# agzu.net
KiCad netlist of a schematic drawn in Altium Designer
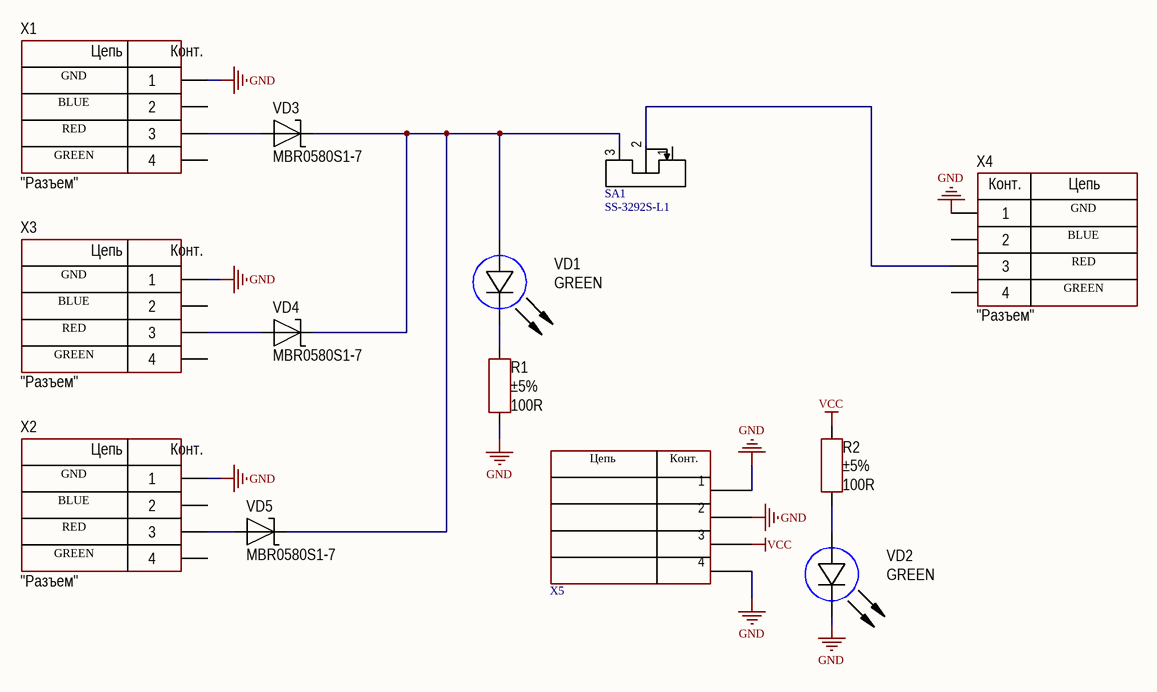
[diagram p0: agzu.SchDoc]

(export (version "E")
  (design (tool "Eeschema 10.0.6"))
  (components
    (comp (ref "R1")
      (value "100R")
      (footprint "RES: 0603")
      (fields
        (field (name "MANUFACTURER") "Yageo")
        (field (name "PARTNUMBER") "RC0603JR-07100RL")
        (field (name "VALUEMANUFACTURERPARTNUMBER") "Resistor film, 100R, ±5%, 0603, 0.1W, -55...+125°C")
        (field (name "TOLERANCE") "±5%")
      )
      (libsource (lib "Resistor") (part "Resistor_0603"))
    )
    (comp (ref "R2")
      (value "100R")
      (footprint "RES: 0603")
      (fields
        (field (name "MANUFACTURER") "Yageo")
        (field (name "PARTNUMBER") "RC0603JR-07100RL")
        (field (name "VALUEMANUFACTURERPARTNUMBER") "Resistor film, 100R, ±5%, 0603, 0.1W, -55...+125°C")
        (field (name "TOLERANCE") "±5%")
      )
      (libsource (lib "Resistor") (part "Resistor_0603"))
    )
    (comp (ref "SA1")
      (value "SS-3292S-L1")
      (footprint "SS-3292S-L1")
      (libsource (lib "switch") (part "SS-3292S-L1"))
    )
    (comp (ref "VD1")
      (value "~")
      (footprint "LED: 0805G")
      (fields
        (field (name "VALUEMANUFACTURERPARTNUMBER") "LED, *, *, *, -55...+150°C")
        (field (name "COLOR") "GREEN")
      )
      (libsource (lib "Diode") (part "LED_single"))
    )
    (comp (ref "VD2")
      (value "~")
      (footprint "LED: 1206R")
      (fields
        (field (name "VALUEMANUFACTURERPARTNUMBER") "LED, *, *, *, -55...+150°C")
        (field (name "COLOR") "GREEN")
      )
      (libsource (lib "Diode") (part "LED_single"))
    )
    (comp (ref "VD3")
      (value "~")
      (footprint "DIODE: SOD523")
      (fields
        (field (name "MANUFACTURER") "Diodes Incorporated")
        (field (name "VALUEMANUFACTURERPARTNUMBER") "Schottky diode, 80V, 500mA, 1V, 15pF, SOD-123, -55...+150°C")
        (field (name "VOLTAGE") "80V")
        (field (name "PARTNUMBER") "MBR0580S1-7")
      )
      (libsource (lib "Diode") (part "Schottky_single"))
    )
    (comp (ref "VD4")
      (value "~")
      (footprint "DIODE: SOD523")
      (fields
        (field (name "MANUFACTURER") "Diodes Incorporated")
        (field (name "VALUEMANUFACTURERPARTNUMBER") "Schottky diode, 80V, 500mA, 1V, 15pF, SOD-123, -55...+150°C")
        (field (name "VOLTAGE") "80V")
        (field (name "PARTNUMBER") "MBR0580S1-7")
      )
      (libsource (lib "Diode") (part "Schottky_single"))
    )
    (comp (ref "VD5")
      (value "~")
      (footprint "DIODE: SOD523")
      (fields
        (field (name "MANUFACTURER") "Diodes Incorporated")
        (field (name "VALUEMANUFACTURERPARTNUMBER") "Schottky diode, 80V, 500mA, 1V, 15pF, SOD-123, -55...+150°C")
        (field (name "VOLTAGE") "80V")
        (field (name "PARTNUMBER") "MBR0580S1-7")
      )
      (libsource (lib "Diode") (part "Schottky_single"))
    )
    (comp (ref "X1")
      (value "~")
      (footprint "CON: PBS-4 R")
      (fields
        (field (name "MANUFACTURER") "Connfly")
        (field (name "VALUEMANUFACTURERPARTNUMBER") "Connector, 4pin, 2.54mm, 500VAC, 3A")
        (field (name "PARTNUMBER") "PBS-4")
        (field (name "COMMENTTEXT") "\"Разъем\"")
      )
      (libsource (lib "Connector") (part "PBS-4"))
    )
    (comp (ref "X2")
      (value "~")
      (footprint "CON: PBS-4 R")
      (fields
        (field (name "MANUFACTURER") "Connfly")
        (field (name "VALUEMANUFACTURERPARTNUMBER") "Connector, 4pin, 2.54mm, 500VAC, 3A")
        (field (name "PARTNUMBER") "PBS-4")
        (field (name "COMMENTTEXT") "\"Разъем\"")
      )
      (libsource (lib "Connector") (part "PBS-4"))
    )
    (comp (ref "X3")
      (value "~")
      (footprint "CON: PBS-4 R")
      (fields
        (field (name "MANUFACTURER") "Connfly")
        (field (name "VALUEMANUFACTURERPARTNUMBER") "Connector, 4pin, 2.54mm, 500VAC, 3A")
        (field (name "PARTNUMBER") "PBS-4")
        (field (name "COMMENTTEXT") "\"Разъем\"")
      )
      (libsource (lib "Connector") (part "PBS-4"))
    )
    (comp (ref "X4")
      (value "~")
      (footprint "4PLS RIGHT ANGLE 2")
      (fields
        (field (name "MANUFACTURER") "Connfly")
        (field (name "VALUEMANUFACTURERPARTNUMBER") "Connector, 4pin, 2.54mm, 500VAC, 3A")
        (field (name "PARTNUMBER") "PLS-4")
        (field (name "COMMENTTEXT") "\"Разъем\"")
      )
      (libsource (lib "Connector") (part "PLS-4"))
    )
    (comp (ref "X5")
      (value "PBS-4 cut")
      (footprint "PBS-4 CUT")
      (libsource (lib "conect") (part "PBS-4 cut"))
    )
  )
  (nets
    (net (code "1") (name "GND") (class "Default")
      (node (ref "R1") (pin "1") (pinfunction "1_1") (pintype "passive"))
      (node (ref "VD2") (pin "2") (pinfunction "C_2") (pintype "passive"))
      (node (ref "X1") (pin "1") (pinfunction "1_1") (pintype "passive"))
      (node (ref "X2") (pin "1") (pinfunction "1_1") (pintype "passive"))
      (node (ref "X3") (pin "1") (pinfunction "1_1") (pintype "passive"))
      (node (ref "X4") (pin "1") (pinfunction "1_1") (pintype "passive"))
      (node (ref "X5") (pin "1") (pinfunction "1_1") (pintype "passive"))
      (node (ref "X5") (pin "2") (pinfunction "2_2") (pintype "passive"))
      (node (ref "X5") (pin "4") (pinfunction "4_4") (pintype "passive"))
    )
    (net (code "2") (name "Net-(SA1-Pad2)") (class "Default")
      (node (ref "SA1") (pin "2") (pinfunction "2_2") (pintype "passive"))
      (node (ref "X4") (pin "3") (pinfunction "3_3") (pintype "power_in"))
    )
    (net (code "3") (name "Net-(VD1-A)") (class "Default")
      (node (ref "SA1") (pin "3") (pinfunction "3_3") (pintype "passive"))
      (node (ref "VD1") (pin "1") (pinfunction "A_1") (pintype "passive"))
      (node (ref "VD3") (pin "2") (pinfunction "2_2") (pintype "passive"))
      (node (ref "VD4") (pin "2") (pinfunction "2_2") (pintype "passive"))
      (node (ref "VD5") (pin "2") (pinfunction "2_2") (pintype "passive"))
    )
    (net (code "4") (name "Net-(VD1-C)") (class "Default")
      (node (ref "R1") (pin "2") (pinfunction "2_2") (pintype "passive"))
      (node (ref "VD1") (pin "2") (pinfunction "C_2") (pintype "passive"))
    )
    (net (code "5") (name "Net-(VD2-A)") (class "Default")
      (node (ref "R2") (pin "1") (pinfunction "1_1") (pintype "passive"))
      (node (ref "VD2") (pin "1") (pinfunction "A_1") (pintype "passive"))
    )
    (net (code "6") (name "Net-(VD3-Pad1)") (class "Default")
      (node (ref "VD3") (pin "1") (pinfunction "1_1") (pintype "passive"))
      (node (ref "X1") (pin "3") (pinfunction "3_3") (pintype "power_in"))
    )
    (net (code "7") (name "Net-(VD4-Pad1)") (class "Default")
      (node (ref "VD4") (pin "1") (pinfunction "1_1") (pintype "passive"))
      (node (ref "X3") (pin "3") (pinfunction "3_3") (pintype "power_in"))
    )
    (net (code "8") (name "Net-(VD5-Pad1)") (class "Default")
      (node (ref "VD5") (pin "1") (pinfunction "1_1") (pintype "passive"))
      (node (ref "X2") (pin "3") (pinfunction "3_3") (pintype "power_in"))
    )
    (net (code "9") (name "VCC") (class "Default")
      (node (ref "R2") (pin "2") (pinfunction "2_2") (pintype "passive"))
      (node (ref "X5") (pin "3") (pinfunction "3_3") (pintype "passive"))
    )
    (net (code "10") (name "unconnected-(SA1-Pad1)") (class "Default")
      (node (ref "SA1") (pin "1") (pinfunction "1_1") (pintype "passive"))
    )
    (net (code "11") (name "unconnected-(X1-Pad2)") (class "Default")
      (node (ref "X1") (pin "2") (pinfunction "2_2") (pintype "passive"))
    )
    (net (code "12") (name "unconnected-(X1-Pad4)") (class "Default")
      (node (ref "X1") (pin "4") (pinfunction "4_4") (pintype "power_in"))
    )
    (net (code "13") (name "unconnected-(X2-Pad2)") (class "Default")
      (node (ref "X2") (pin "2") (pinfunction "2_2") (pintype "passive"))
    )
    (net (code "14") (name "unconnected-(X2-Pad4)") (class "Default")
      (node (ref "X2") (pin "4") (pinfunction "4_4") (pintype "power_in"))
    )
    (net (code "15") (name "unconnected-(X3-Pad2)") (class "Default")
      (node (ref "X3") (pin "2") (pinfunction "2_2") (pintype "passive"))
    )
    (net (code "16") (name "unconnected-(X3-Pad4)") (class "Default")
      (node (ref "X3") (pin "4") (pinfunction "4_4") (pintype "power_in"))
    )
    (net (code "17") (name "unconnected-(X4-Pad2)") (class "Default")
      (node (ref "X4") (pin "2") (pinfunction "2_2") (pintype "passive"))
    )
    (net (code "18") (name "unconnected-(X4-Pad4)") (class "Default")
      (node (ref "X4") (pin "4") (pinfunction "4_4") (pintype "power_in"))
    )
  )
)
